# ESP07_SHIELD.net
KiCad netlist of a schematic drawn in Altium Designer
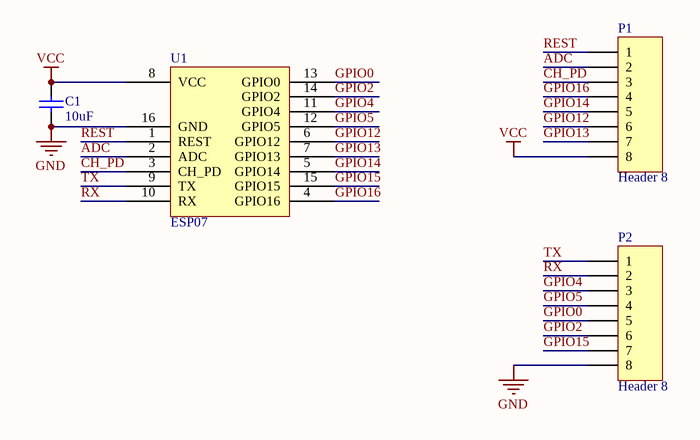
[diagram p0: ESP07_SHIELD.SchDoc]

(export (version "E")
  (design (tool "Eeschema 10.0.6"))
  (components
    (comp (ref "C1")
      (value "10uF")
      (footprint "6-0805_M")
      (description "Capacitor")
      (fields (field (name "Comment") "Cap") (field (name "PUBLISHER") "Altium Limited"))
      (libsource (lib "ESP07") (part "Cap"))
    )
    (comp (ref "P1")
      (value "Header 8")
      (footprint "HDR1X8")
      (description "Header, 8-Pin")
      (fields (field (name "PUBLISHER") "Altium Limited"))
      (libsource (lib "ESP07") (part "Header 8"))
    )
    (comp (ref "P2")
      (value "Header 8")
      (footprint "HDR1X8")
      (description "Header, 8-Pin")
      (fields (field (name "PUBLISHER") "Altium Limited"))
      (libsource (lib "ESP07") (part "Header 8"))
    )
    (comp (ref "U1")
      (value "ESP07")
      (footprint "ESP07")
      (description "ESP8266")
      (libsource (lib "ESP07") (part "ESP07"))
    )
  )
  (nets
    (net (code "1") (name "/ADC") (class "Default")
      (node (ref "P1") (pin "2") (pinfunction "2_2") (pintype "passive"))
      (node (ref "U1") (pin "2") (pinfunction "ADC_2") (pintype "passive"))
    )
    (net (code "2") (name "/CH_PD") (class "Default")
      (node (ref "P1") (pin "3") (pinfunction "3_3") (pintype "passive"))
      (node (ref "U1") (pin "3") (pinfunction "CH_PD_3") (pintype "passive"))
    )
    (net (code "3") (name "/GPIO0") (class "Default")
      (node (ref "P2") (pin "5") (pinfunction "5_5") (pintype "passive"))
      (node (ref "U1") (pin "13") (pinfunction "GPIO0_13") (pintype "passive"))
    )
    (net (code "4") (name "/GPIO2") (class "Default")
      (node (ref "P2") (pin "6") (pinfunction "6_6") (pintype "passive"))
      (node (ref "U1") (pin "14") (pinfunction "GPIO2_14") (pintype "passive"))
    )
    (net (code "5") (name "/GPIO4") (class "Default")
      (node (ref "P2") (pin "3") (pinfunction "3_3") (pintype "passive"))
      (node (ref "U1") (pin "11") (pinfunction "GPIO4_11") (pintype "passive"))
    )
    (net (code "6") (name "/GPIO5") (class "Default")
      (node (ref "P2") (pin "4") (pinfunction "4_4") (pintype "passive"))
      (node (ref "U1") (pin "12") (pinfunction "GPIO5_12") (pintype "passive"))
    )
    (net (code "7") (name "/GPIO12") (class "Default")
      (node (ref "P1") (pin "6") (pinfunction "6_6") (pintype "passive"))
      (node (ref "U1") (pin "6") (pinfunction "GPIO12_6") (pintype "passive"))
    )
    (net (code "8") (name "/GPIO13") (class "Default")
      (node (ref "P1") (pin "7") (pinfunction "7_7") (pintype "passive"))
      (node (ref "U1") (pin "7") (pinfunction "GPIO13_7") (pintype "passive"))
    )
    (net (code "9") (name "/GPIO14") (class "Default")
      (node (ref "P1") (pin "5") (pinfunction "5_5") (pintype "passive"))
      (node (ref "U1") (pin "5") (pinfunction "GPIO14_5") (pintype "passive"))
    )
    (net (code "10") (name "/GPIO15") (class "Default")
      (node (ref "P2") (pin "7") (pinfunction "7_7") (pintype "passive"))
      (node (ref "U1") (pin "15") (pinfunction "GPIO15_15") (pintype "passive"))
    )
    (net (code "11") (name "/GPIO16") (class "Default")
      (node (ref "P1") (pin "4") (pinfunction "4_4") (pintype "passive"))
      (node (ref "U1") (pin "4") (pinfunction "GPIO16_4") (pintype "passive"))
    )
    (net (code "12") (name "/REST") (class "Default")
      (node (ref "P1") (pin "1") (pinfunction "1_1") (pintype "passive"))
      (node (ref "U1") (pin "1") (pinfunction "REST_1") (pintype "passive"))
    )
    (net (code "13") (name "/RX") (class "Default")
      (node (ref "P2") (pin "2") (pinfunction "2_2") (pintype "passive"))
      (node (ref "U1") (pin "10") (pinfunction "RX_10") (pintype "passive"))
    )
    (net (code "14") (name "/TX") (class "Default")
      (node (ref "P2") (pin "1") (pinfunction "1_1") (pintype "passive"))
      (node (ref "U1") (pin "9") (pinfunction "TX_9") (pintype "passive"))
    )
    (net (code "15") (name "GND") (class "Default")
      (node (ref "C1") (pin "1") (pinfunction "1_1") (pintype "passive"))
      (node (ref "P2") (pin "8") (pinfunction "8_8") (pintype "passive"))
      (node (ref "U1") (pin "16") (pinfunction "GND_16") (pintype "passive"))
    )
    (net (code "16") (name "VCC") (class "Default")
      (node (ref "C1") (pin "2") (pinfunction "2_2") (pintype "passive"))
      (node (ref "P1") (pin "8") (pinfunction "8_8") (pintype "passive"))
      (node (ref "U1") (pin "8") (pinfunction "VCC_8") (pintype "passive"))
    )
  )
)
